# bue_steuerung.net
KiCad netlist of a schematic drawn in EAGLE
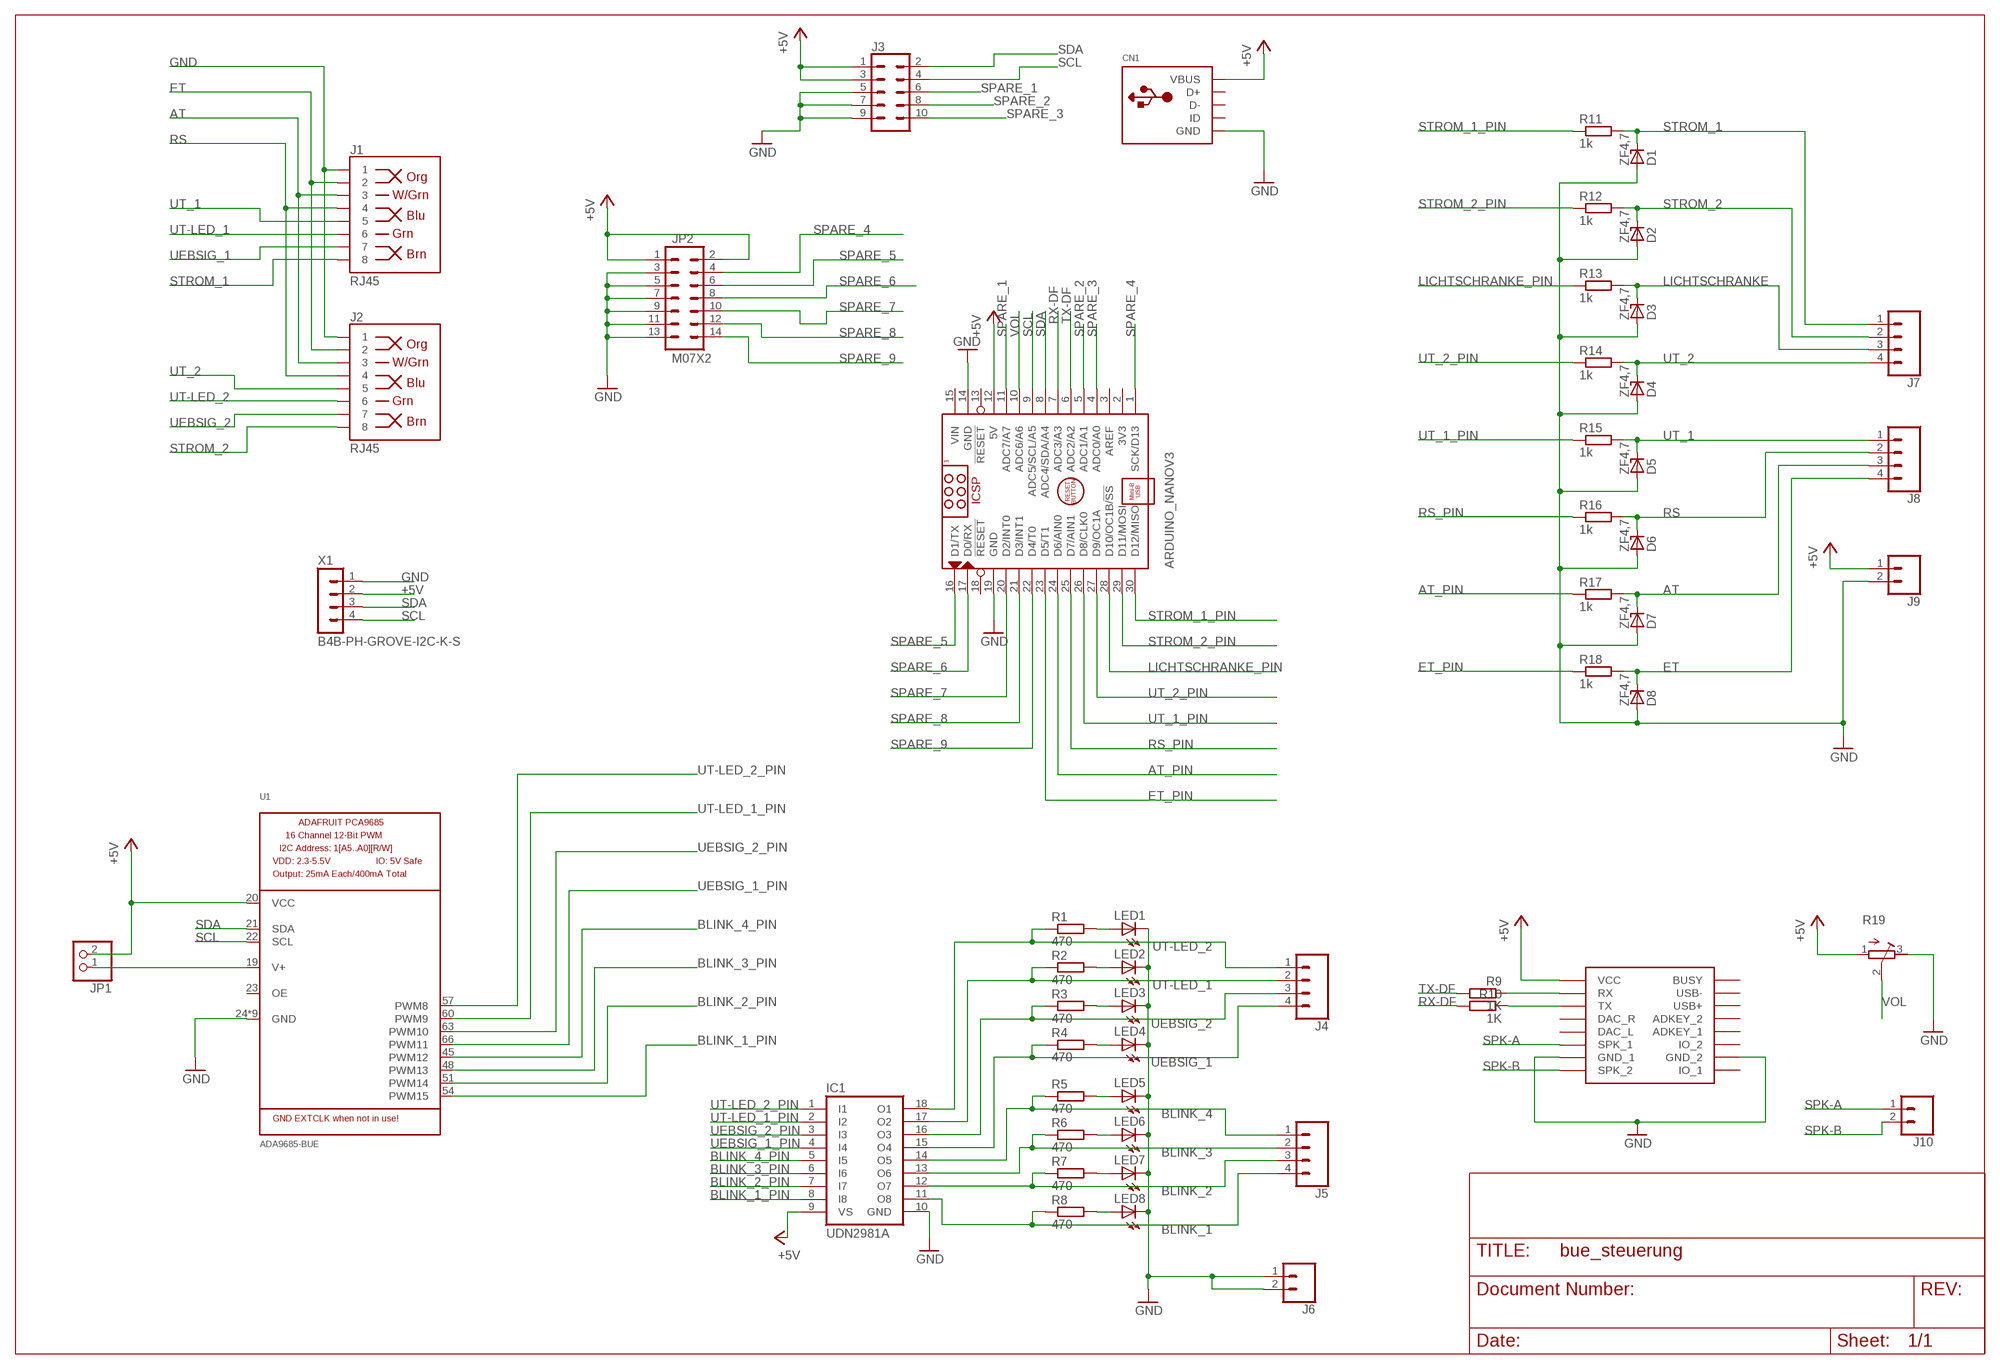
[diagram p0: schematic, sheet 1]

(export (version "E")
  (design (tool "Eeschema 10.0.6"))
  (components
    (comp (ref "ARDUINO_NANOV3")
      (value "ARDUINO_NANO")
      (footprint "eagle-import:ARDUINO_NANO")
      (libsource (lib "eagle-import") (part "ARDUINO_NANO"))
    )
    (comp (ref "CN1")
      (value "USBMOLEX")
      (footprint "eagle-import:USB-MINIB-THM-MOLEX")
      (libsource (lib "eagle-import") (part "USBMOLEX"))
    )
    (comp (ref "D1")
      (value "ZF4,7")
      (footprint "eagle-import:ZDIO-7.5")
      (libsource (lib "eagle-import") (part "ZENER-DIODEZD-7.5"))
    )
    (comp (ref "D2")
      (value "ZF4,7")
      (footprint "eagle-import:ZDIO-7.5")
      (libsource (lib "eagle-import") (part "ZENER-DIODEZD-7.5"))
    )
    (comp (ref "D3")
      (value "ZF4,7")
      (footprint "eagle-import:ZDIO-7.5")
      (libsource (lib "eagle-import") (part "ZENER-DIODEZD-7.5"))
    )
    (comp (ref "D4")
      (value "ZF4,7")
      (footprint "eagle-import:ZDIO-7.5")
      (libsource (lib "eagle-import") (part "ZENER-DIODEZD-7.5"))
    )
    (comp (ref "D5")
      (value "ZF4,7")
      (footprint "eagle-import:ZDIO-7.5")
      (libsource (lib "eagle-import") (part "ZENER-DIODEZD-7.5"))
    )
    (comp (ref "D6")
      (value "ZF4,7")
      (footprint "eagle-import:ZDIO-7.5")
      (libsource (lib "eagle-import") (part "ZENER-DIODEZD-7.5"))
    )
    (comp (ref "D7")
      (value "ZF4,7")
      (footprint "eagle-import:ZDIO-7.5")
      (libsource (lib "eagle-import") (part "ZENER-DIODEZD-7.5"))
    )
    (comp (ref "D8")
      (value "ZF4,7")
      (footprint "eagle-import:ZDIO-7.5")
      (libsource (lib "eagle-import") (part "ZENER-DIODEZD-7.5"))
    )
    (comp (ref "IC1")
      (value "UDN2981A")
      (footprint "eagle-import:DIL18")
      (libsource (lib "eagle-import") (part "UDN298A1"))
    )
    (comp (ref "J1")
      (value "RJ45")
      (footprint "eagle-import:RJ45-8")
      (libsource (lib "eagle-import") (part "RJ45-8"))
    )
    (comp (ref "J2")
      (value "RJ45")
      (footprint "eagle-import:RJ45-8")
      (libsource (lib "eagle-import") (part "RJ45-8"))
    )
    (comp (ref "J3")
      (value "CONN_05X2SHD")
      (footprint "eagle-import:2X5-SHROUDED")
      (libsource (lib "eagle-import") (part "CONN_05X2SHD"))
    )
    (comp (ref "J4")
      (value "CONN_04SCREW")
      (footprint "eagle-import:SCREWTERMINAL-3.5MM-4")
      (libsource (lib "eagle-import") (part "CONN_04SCREW"))
    )
    (comp (ref "J5")
      (value "CONN_04SCREW")
      (footprint "eagle-import:SCREWTERMINAL-3.5MM-4")
      (libsource (lib "eagle-import") (part "CONN_04SCREW"))
    )
    (comp (ref "J6")
      (value "CONN_023.5MM")
      (footprint "eagle-import:SCREWTERMINAL-3.5MM-2")
      (libsource (lib "eagle-import") (part "CONN_023.5MM"))
    )
    (comp (ref "J7")
      (value "CONN_04SCREW")
      (footprint "eagle-import:SCREWTERMINAL-3.5MM-4")
      (libsource (lib "eagle-import") (part "CONN_04SCREW"))
    )
    (comp (ref "J8")
      (value "CONN_04SCREW")
      (footprint "eagle-import:SCREWTERMINAL-3.5MM-4")
      (libsource (lib "eagle-import") (part "CONN_04SCREW"))
    )
    (comp (ref "J9")
      (value "CONN_023.5MM")
      (footprint "eagle-import:SCREWTERMINAL-3.5MM-2")
      (libsource (lib "eagle-import") (part "CONN_023.5MM"))
    )
    (comp (ref "J10")
      (value "CONN_023.5MM")
      (footprint "eagle-import:SCREWTERMINAL-3.5MM-2")
      (libsource (lib "eagle-import") (part "CONN_023.5MM"))
    )
    (comp (ref "JP1")
      (value "PINHD-1X2")
      (footprint "eagle-import:1X02")
      (libsource (lib "eagle-import") (part "PINHD-1X2"))
    )
    (comp (ref "JP2")
      (value "M07X2")
      (footprint "eagle-import:2X7-SHROUDED")
      (libsource (lib "eagle-import") (part "M07X2"))
    )
    (comp (ref "LED1")
      (value "LED3MM")
      (footprint "eagle-import:LED3MM")
      (libsource (lib "eagle-import") (part "LED3MM"))
    )
    (comp (ref "LED2")
      (value "LED3MM")
      (footprint "eagle-import:LED3MM")
      (libsource (lib "eagle-import") (part "LED3MM"))
    )
    (comp (ref "LED3")
      (value "LED3MM")
      (footprint "eagle-import:LED3MM")
      (libsource (lib "eagle-import") (part "LED3MM"))
    )
    (comp (ref "LED4")
      (value "LED3MM")
      (footprint "eagle-import:LED3MM")
      (libsource (lib "eagle-import") (part "LED3MM"))
    )
    (comp (ref "LED5")
      (value "LED3MM")
      (footprint "eagle-import:LED3MM")
      (libsource (lib "eagle-import") (part "LED3MM"))
    )
    (comp (ref "LED6")
      (value "LED3MM")
      (footprint "eagle-import:LED3MM")
      (libsource (lib "eagle-import") (part "LED3MM"))
    )
    (comp (ref "LED7")
      (value "LED3MM")
      (footprint "eagle-import:LED3MM")
      (libsource (lib "eagle-import") (part "LED3MM"))
    )
    (comp (ref "LED8")
      (value "LED3MM")
      (footprint "eagle-import:LED3MM")
      (libsource (lib "eagle-import") (part "LED3MM"))
    )
    (comp (ref "R1")
      (value "470")
      (footprint "eagle-import:0207_7")
      (libsource (lib "eagle-import") (part "resistor@1_R-EU_0207/7"))
    )
    (comp (ref "R2")
      (value "470")
      (footprint "eagle-import:0207_7")
      (libsource (lib "eagle-import") (part "resistor@1_R-EU_0207/7"))
    )
    (comp (ref "R3")
      (value "470")
      (footprint "eagle-import:0207_7")
      (libsource (lib "eagle-import") (part "resistor@1_R-EU_0207/7"))
    )
    (comp (ref "R4")
      (value "470")
      (footprint "eagle-import:0207_7")
      (libsource (lib "eagle-import") (part "resistor@1_R-EU_0207/7"))
    )
    (comp (ref "R5")
      (value "470")
      (footprint "eagle-import:0207_7")
      (libsource (lib "eagle-import") (part "resistor@1_R-EU_0207/7"))
    )
    (comp (ref "R6")
      (value "470")
      (footprint "eagle-import:0207_7")
      (libsource (lib "eagle-import") (part "resistor@1_R-EU_0207/7"))
    )
    (comp (ref "R7")
      (value "470")
      (footprint "eagle-import:0207_7")
      (libsource (lib "eagle-import") (part "resistor@1_R-EU_0207/7"))
    )
    (comp (ref "R8")
      (value "470")
      (footprint "eagle-import:0207_7")
      (libsource (lib "eagle-import") (part "resistor@1_R-EU_0207/7"))
    )
    (comp (ref "R9")
      (value "1K")
      (footprint "eagle-import:0207_7")
      (libsource (lib "eagle-import") (part "R-EU_0207/7"))
    )
    (comp (ref "R10")
      (value "1K")
      (footprint "eagle-import:0207_7")
      (libsource (lib "eagle-import") (part "R-EU_0207/7"))
    )
    (comp (ref "R11")
      (value "1k")
      (footprint "eagle-import:0207_7")
      (libsource (lib "eagle-import") (part "resistor@1_R-EU_0207/7"))
    )
    (comp (ref "R12")
      (value "1k")
      (footprint "eagle-import:0207_7")
      (libsource (lib "eagle-import") (part "resistor@1_R-EU_0207/7"))
    )
    (comp (ref "R13")
      (value "1k")
      (footprint "eagle-import:0207_7")
      (libsource (lib "eagle-import") (part "resistor@1_R-EU_0207/7"))
    )
    (comp (ref "R14")
      (value "1k")
      (footprint "eagle-import:0207_7")
      (libsource (lib "eagle-import") (part "resistor@1_R-EU_0207/7"))
    )
    (comp (ref "R15")
      (value "1k")
      (footprint "eagle-import:0207_7")
      (libsource (lib "eagle-import") (part "resistor@1_R-EU_0207/7"))
    )
    (comp (ref "R16")
      (value "1k")
      (footprint "eagle-import:0207_7")
      (libsource (lib "eagle-import") (part "resistor@1_R-EU_0207/7"))
    )
    (comp (ref "R17")
      (value "1k")
      (footprint "eagle-import:0207_7")
      (libsource (lib "eagle-import") (part "resistor@1_R-EU_0207/7"))
    )
    (comp (ref "R18")
      (value "1k")
      (footprint "eagle-import:0207_7")
      (libsource (lib "eagle-import") (part "resistor@1_R-EU_0207/7"))
    )
    (comp (ref "R19")
      (value "R-TRIMM64Y")
      (footprint "eagle-import:RTRIM64Y")
      (libsource (lib "eagle-import") (part "R-TRIMM64Y"))
    )
    (comp (ref "U1")
      (value "ADA9685-BUE")
      (footprint "eagle-import:ADA9685-BUE")
      (libsource (lib "eagle-import") (part "ADA9685-BUE"))
    )
    (comp (ref "U2")
      (value "DFPLAYER")
      (footprint "eagle-import:DFPLAYER")
      (libsource (lib "eagle-import") (part "DFPLAYER"))
    )
    (comp (ref "X1")
      (value "B4B-PH-GROVE-I2C-K-S")
      (footprint "eagle-import:B4B-PH-K-S")
      (libsource (lib "eagle-import") (part "B4B-PH-GROVE-I2C-K-S"))
    )
  )
  (nets
    (net (code "1") (name "+5V") (class "Default")
      (node (ref "ARDUINO_NANOV3") (pin "12") (pinfunction "5V_12") (pintype "power_in"))
      (node (ref "CN1") (pin "VBUS") (pinfunction "VBUS_VBUS") (pintype "power_in"))
      (node (ref "IC1") (pin "9") (pinfunction "VS_9") (pintype "passive"))
      (node (ref "J3") (pin "1") (pinfunction "1_1") (pintype "passive"))
      (node (ref "J3") (pin "3") (pinfunction "3_3") (pintype "passive"))
      (node (ref "J9") (pin "1") (pinfunction "1_1") (pintype "passive"))
      (node (ref "JP1") (pin "2") (pinfunction "2_2") (pintype "passive"))
      (node (ref "JP2") (pin "1") (pinfunction "1_1") (pintype "passive"))
      (node (ref "JP2") (pin "2") (pinfunction "2_2") (pintype "passive"))
      (node (ref "R19") (pin "1") (pinfunction "A_1") (pintype "passive"))
      (node (ref "U1") (pin "20") (pinfunction "VCC_20") (pintype "power_in"))
      (node (ref "U2") (pin "VCC") (pinfunction "VCC_VCC") (pintype "bidirectional"))
      (node (ref "X1") (pin "2") (pinfunction "3_2") (pintype "passive"))
    )
    (net (code "2") (name "/AT") (class "Default")
      (node (ref "D7") (pin "C") (pinfunction "C_C") (pintype "passive"))
      (node (ref "J1") (pin "3") (pinfunction "3_3") (pintype "bidirectional"))
      (node (ref "J2") (pin "3") (pinfunction "3_3") (pintype "bidirectional"))
      (node (ref "J8") (pin "3") (pinfunction "3_3") (pintype "passive"))
      (node (ref "R17") (pin "2") (pinfunction "2_2") (pintype "passive"))
    )
    (net (code "3") (name "/AT_PIN") (class "Default")
      (node (ref "ARDUINO_NANOV3") (pin "24") (pinfunction "D6/AIN0_24") (pintype "bidirectional"))
      (node (ref "R17") (pin "1") (pinfunction "1_1") (pintype "passive"))
    )
    (net (code "4") (name "/BLINK_1") (class "Default")
      (node (ref "IC1") (pin "11") (pinfunction "O8_11") (pintype "open_collector"))
      (node (ref "J5") (pin "4") (pinfunction "4_4") (pintype "passive"))
      (node (ref "R8") (pin "1") (pinfunction "1_1") (pintype "passive"))
    )
    (net (code "5") (name "/BLINK_1_PIN") (class "Default")
      (node (ref "IC1") (pin "8") (pinfunction "I8_8") (pintype "input"))
      (node (ref "U1") (pin "54") (pinfunction "PWM15_54") (pintype "output"))
    )
    (net (code "6") (name "/BLINK_2") (class "Default")
      (node (ref "IC1") (pin "12") (pinfunction "O7_12") (pintype "open_collector"))
      (node (ref "J5") (pin "3") (pinfunction "3_3") (pintype "passive"))
      (node (ref "R7") (pin "1") (pinfunction "1_1") (pintype "passive"))
    )
    (net (code "7") (name "/BLINK_2_PIN") (class "Default")
      (node (ref "IC1") (pin "7") (pinfunction "I7_7") (pintype "input"))
      (node (ref "U1") (pin "51") (pinfunction "PWM14_51") (pintype "output"))
    )
    (net (code "8") (name "/BLINK_3") (class "Default")
      (node (ref "IC1") (pin "13") (pinfunction "O6_13") (pintype "open_collector"))
      (node (ref "J5") (pin "2") (pinfunction "2_2") (pintype "passive"))
      (node (ref "R6") (pin "1") (pinfunction "1_1") (pintype "passive"))
    )
    (net (code "9") (name "/BLINK_3_PIN") (class "Default")
      (node (ref "IC1") (pin "6") (pinfunction "I6_6") (pintype "input"))
      (node (ref "U1") (pin "48") (pinfunction "PWM13_48") (pintype "output"))
    )
    (net (code "10") (name "/BLINK_4") (class "Default")
      (node (ref "IC1") (pin "14") (pinfunction "O5_14") (pintype "open_collector"))
      (node (ref "J5") (pin "1") (pinfunction "1_1") (pintype "passive"))
      (node (ref "R5") (pin "1") (pinfunction "1_1") (pintype "passive"))
    )
    (net (code "11") (name "/BLINK_4_PIN") (class "Default")
      (node (ref "IC1") (pin "5") (pinfunction "I5_5") (pintype "input"))
      (node (ref "U1") (pin "45") (pinfunction "PWM12_45") (pintype "output"))
    )
    (net (code "12") (name "/ET") (class "Default")
      (node (ref "D8") (pin "C") (pinfunction "C_C") (pintype "passive"))
      (node (ref "J1") (pin "2") (pinfunction "2_2") (pintype "bidirectional"))
      (node (ref "J2") (pin "2") (pinfunction "2_2") (pintype "bidirectional"))
      (node (ref "J8") (pin "4") (pinfunction "4_4") (pintype "passive"))
      (node (ref "R18") (pin "2") (pinfunction "2_2") (pintype "passive"))
    )
    (net (code "13") (name "/ET_PIN") (class "Default")
      (node (ref "ARDUINO_NANOV3") (pin "23") (pinfunction "D5/T1_23") (pintype "bidirectional"))
      (node (ref "R18") (pin "1") (pinfunction "1_1") (pintype "passive"))
    )
    (net (code "14") (name "/LICHTSCHRANKE") (class "Default")
      (node (ref "D3") (pin "C") (pinfunction "C_C") (pintype "passive"))
      (node (ref "J7") (pin "3") (pinfunction "3_3") (pintype "passive"))
      (node (ref "R13") (pin "2") (pinfunction "2_2") (pintype "passive"))
    )
    (net (code "15") (name "/LICHTSCHRANKE_PIN") (class "Default")
      (node (ref "ARDUINO_NANOV3") (pin "28") (pinfunction "D10/OC1B/~{SS}_28") (pintype "bidirectional"))
      (node (ref "R13") (pin "1") (pinfunction "1_1") (pintype "passive"))
    )
    (net (code "16") (name "/RS") (class "Default")
      (node (ref "D6") (pin "C") (pinfunction "C_C") (pintype "passive"))
      (node (ref "J1") (pin "4") (pinfunction "4_4") (pintype "bidirectional"))
      (node (ref "J2") (pin "4") (pinfunction "4_4") (pintype "bidirectional"))
      (node (ref "J8") (pin "2") (pinfunction "2_2") (pintype "passive"))
      (node (ref "R16") (pin "2") (pinfunction "2_2") (pintype "passive"))
    )
    (net (code "17") (name "/RS_PIN") (class "Default")
      (node (ref "ARDUINO_NANOV3") (pin "25") (pinfunction "D7/AIN1_25") (pintype "bidirectional"))
      (node (ref "R16") (pin "1") (pinfunction "1_1") (pintype "passive"))
    )
    (net (code "18") (name "/RX-DF") (class "Default")
      (node (ref "ARDUINO_NANOV3") (pin "7") (pinfunction "ADC3/A3_7") (pintype "bidirectional"))
      (node (ref "R10") (pin "2") (pinfunction "2_2") (pintype "passive"))
    )
    (net (code "19") (name "/SCL") (class "Default")
      (node (ref "ARDUINO_NANOV3") (pin "9") (pinfunction "ADC5/SCL/A5_9") (pintype "bidirectional"))
      (node (ref "J3") (pin "4") (pinfunction "4_4") (pintype "passive"))
      (node (ref "U1") (pin "22") (pinfunction "SCL_22") (pintype "bidirectional"))
      (node (ref "X1") (pin "4") (pinfunction "1_4") (pintype "passive"))
    )
    (net (code "20") (name "/SDA") (class "Default")
      (node (ref "ARDUINO_NANOV3") (pin "8") (pinfunction "ADC4/SDA/A4_8") (pintype "bidirectional"))
      (node (ref "J3") (pin "2") (pinfunction "2_2") (pintype "passive"))
      (node (ref "U1") (pin "21") (pinfunction "SDA_21") (pintype "bidirectional"))
      (node (ref "X1") (pin "3") (pinfunction "2_3") (pintype "passive"))
    )
    (net (code "21") (name "/SPARE_1") (class "Default")
      (node (ref "ARDUINO_NANOV3") (pin "11") (pinfunction "ADC7/A7_11") (pintype "bidirectional"))
      (node (ref "J3") (pin "6") (pinfunction "6_6") (pintype "passive"))
    )
    (net (code "22") (name "/SPARE_2") (class "Default")
      (node (ref "ARDUINO_NANOV3") (pin "5") (pinfunction "ADC1/A1_5") (pintype "bidirectional"))
      (node (ref "J3") (pin "8") (pinfunction "8_8") (pintype "passive"))
    )
    (net (code "23") (name "/SPARE_3") (class "Default")
      (node (ref "ARDUINO_NANOV3") (pin "4") (pinfunction "ADC0/A0_4") (pintype "bidirectional"))
      (node (ref "J3") (pin "10") (pinfunction "10_10") (pintype "passive"))
    )
    (net (code "24") (name "/SPARE_4") (class "Default")
      (node (ref "ARDUINO_NANOV3") (pin "1") (pinfunction "SCK/D13_1") (pintype "bidirectional"))
      (node (ref "JP2") (pin "4") (pinfunction "4_4") (pintype "passive"))
    )
    (net (code "25") (name "/SPARE_5") (class "Default")
      (node (ref "ARDUINO_NANOV3") (pin "16") (pinfunction "D1/TX_16") (pintype "bidirectional"))
      (node (ref "JP2") (pin "6") (pinfunction "6_6") (pintype "passive"))
    )
    (net (code "26") (name "/SPARE_6") (class "Default")
      (node (ref "ARDUINO_NANOV3") (pin "17") (pinfunction "D0/RX_17") (pintype "bidirectional"))
      (node (ref "JP2") (pin "8") (pinfunction "8_8") (pintype "passive"))
    )
    (net (code "27") (name "/SPARE_7") (class "Default")
      (node (ref "ARDUINO_NANOV3") (pin "20") (pinfunction "D2/INT0_20") (pintype "bidirectional"))
      (node (ref "JP2") (pin "10") (pinfunction "10_10") (pintype "passive"))
    )
    (net (code "28") (name "/SPARE_8") (class "Default")
      (node (ref "ARDUINO_NANOV3") (pin "21") (pinfunction "D3/INT1_21") (pintype "bidirectional"))
      (node (ref "JP2") (pin "12") (pinfunction "12_12") (pintype "passive"))
    )
    (net (code "29") (name "/SPARE_9") (class "Default")
      (node (ref "ARDUINO_NANOV3") (pin "22") (pinfunction "D4/T0_22") (pintype "bidirectional"))
      (node (ref "JP2") (pin "14") (pinfunction "14_14") (pintype "passive"))
    )
    (net (code "30") (name "/SPK-A") (class "Default")
      (node (ref "J10") (pin "1") (pinfunction "1_1") (pintype "passive"))
      (node (ref "U2") (pin "SPK1") (pinfunction "SPK_1_SPK1") (pintype "bidirectional"))
    )
    (net (code "31") (name "/SPK-B") (class "Default")
      (node (ref "J10") (pin "2") (pinfunction "2_2") (pintype "passive"))
      (node (ref "U2") (pin "SPK2") (pinfunction "SPK_2_SPK2") (pintype "bidirectional"))
    )
    (net (code "32") (name "/STROM_1") (class "Default")
      (node (ref "D1") (pin "C") (pinfunction "C_C") (pintype "passive"))
      (node (ref "J1") (pin "8") (pinfunction "8_8") (pintype "bidirectional"))
      (node (ref "J7") (pin "1") (pinfunction "1_1") (pintype "passive"))
      (node (ref "R11") (pin "2") (pinfunction "2_2") (pintype "passive"))
    )
    (net (code "33") (name "/STROM_1_PIN") (class "Default")
      (node (ref "ARDUINO_NANOV3") (pin "30") (pinfunction "D12/MISO_30") (pintype "bidirectional"))
      (node (ref "R11") (pin "1") (pinfunction "1_1") (pintype "passive"))
    )
    (net (code "34") (name "/STROM_2") (class "Default")
      (node (ref "D2") (pin "C") (pinfunction "C_C") (pintype "passive"))
      (node (ref "J2") (pin "8") (pinfunction "8_8") (pintype "bidirectional"))
      (node (ref "J7") (pin "2") (pinfunction "2_2") (pintype "passive"))
      (node (ref "R12") (pin "2") (pinfunction "2_2") (pintype "passive"))
    )
    (net (code "35") (name "/STROM_2_PIN") (class "Default")
      (node (ref "ARDUINO_NANOV3") (pin "29") (pinfunction "D11/MOSI_29") (pintype "bidirectional"))
      (node (ref "R12") (pin "1") (pinfunction "1_1") (pintype "passive"))
    )
    (net (code "36") (name "/TX-DF") (class "Default")
      (node (ref "ARDUINO_NANOV3") (pin "6") (pinfunction "ADC2/A2_6") (pintype "bidirectional"))
      (node (ref "R9") (pin "2") (pinfunction "2_2") (pintype "passive"))
    )
    (net (code "37") (name "/UEBSIG_1") (class "Default")
      (node (ref "IC1") (pin "15") (pinfunction "O4_15") (pintype "open_collector"))
      (node (ref "J1") (pin "7") (pinfunction "7_7") (pintype "bidirectional"))
      (node (ref "J4") (pin "4") (pinfunction "4_4") (pintype "passive"))
      (node (ref "R4") (pin "1") (pinfunction "1_1") (pintype "passive"))
    )
    (net (code "38") (name "/UEBSIG_1_PIN") (class "Default")
      (node (ref "IC1") (pin "4") (pinfunction "I4_4") (pintype "input"))
      (node (ref "U1") (pin "66") (pinfunction "PWM11_66") (pintype "output"))
    )
    (net (code "39") (name "/UEBSIG_2") (class "Default")
      (node (ref "IC1") (pin "16") (pinfunction "O3_16") (pintype "open_collector"))
      (node (ref "J2") (pin "7") (pinfunction "7_7") (pintype "bidirectional"))
      (node (ref "J4") (pin "3") (pinfunction "3_3") (pintype "passive"))
      (node (ref "R3") (pin "1") (pinfunction "1_1") (pintype "passive"))
    )
    (net (code "40") (name "/UEBSIG_2_PIN") (class "Default")
      (node (ref "IC1") (pin "3") (pinfunction "I3_3") (pintype "input"))
      (node (ref "U1") (pin "63") (pinfunction "PWM10_63") (pintype "output"))
    )
    (net (code "41") (name "/UT-LED_1") (class "Default")
      (node (ref "IC1") (pin "17") (pinfunction "O2_17") (pintype "open_collector"))
      (node (ref "J1") (pin "6") (pinfunction "6_6") (pintype "bidirectional"))
      (node (ref "J4") (pin "2") (pinfunction "2_2") (pintype "passive"))
      (node (ref "R2") (pin "1") (pinfunction "1_1") (pintype "passive"))
    )
    (net (code "42") (name "/UT-LED_1_PIN") (class "Default")
      (node (ref "IC1") (pin "2") (pinfunction "I2_2") (pintype "input"))
      (node (ref "U1") (pin "60") (pinfunction "PWM9_60") (pintype "output"))
    )
    (net (code "43") (name "/UT-LED_2") (class "Default")
      (node (ref "IC1") (pin "18") (pinfunction "O1_18") (pintype "open_collector"))
      (node (ref "J2") (pin "6") (pinfunction "6_6") (pintype "bidirectional"))
      (node (ref "J4") (pin "1") (pinfunction "1_1") (pintype "passive"))
      (node (ref "R1") (pin "1") (pinfunction "1_1") (pintype "passive"))
    )
    (net (code "44") (name "/UT-LED_2_PIN") (class "Default")
      (node (ref "IC1") (pin "1") (pinfunction "I1_1") (pintype "input"))
      (node (ref "U1") (pin "57") (pinfunction "PWM8_57") (pintype "output"))
    )
    (net (code "45") (name "/UT_1") (class "Default")
      (node (ref "D5") (pin "C") (pinfunction "C_C") (pintype "passive"))
      (node (ref "J1") (pin "5") (pinfunction "5_5") (pintype "bidirectional"))
      (node (ref "J8") (pin "1") (pinfunction "1_1") (pintype "passive"))
      (node (ref "R15") (pin "2") (pinfunction "2_2") (pintype "passive"))
    )
    (net (code "46") (name "/UT_1_PIN") (class "Default")
      (node (ref "ARDUINO_NANOV3") (pin "26") (pinfunction "D8/CLK0_26") (pintype "bidirectional"))
      (node (ref "R15") (pin "1") (pinfunction "1_1") (pintype "passive"))
    )
    (net (code "47") (name "/UT_2") (class "Default")
      (node (ref "D4") (pin "C") (pinfunction "C_C") (pintype "passive"))
      (node (ref "J2") (pin "5") (pinfunction "5_5") (pintype "bidirectional"))
      (node (ref "J7") (pin "4") (pinfunction "4_4") (pintype "passive"))
      (node (ref "R14") (pin "2") (pinfunction "2_2") (pintype "passive"))
    )
    (net (code "48") (name "/UT_2_PIN") (class "Default")
      (node (ref "ARDUINO_NANOV3") (pin "27") (pinfunction "D9/OC1A_27") (pintype "bidirectional"))
      (node (ref "R14") (pin "1") (pinfunction "1_1") (pintype "passive"))
    )
    (net (code "49") (name "/VIN") (class "Default")
      (node (ref "ARDUINO_NANOV3") (pin "15") (pinfunction "VIN_15") (pintype "power_in"))
    )
    (net (code "50") (name "/VOL") (class "Default")
      (node (ref "ARDUINO_NANOV3") (pin "10") (pinfunction "ADC6/A6_10") (pintype "bidirectional"))
      (node (ref "R19") (pin "2") (pinfunction "S_2") (pintype "passive"))
    )
    (net (code "51") (name "GND") (class "Default")
      (node (ref "ARDUINO_NANOV3") (pin "14") (pinfunction "GND_14") (pintype "power_in"))
      (node (ref "ARDUINO_NANOV3") (pin "19") (pinfunction "GND_19") (pintype "power_in"))
      (node (ref "CN1") (pin "GND") (pinfunction "GND_GND") (pintype "power_in"))
      (node (ref "D1") (pin "A") (pinfunction "A_A") (pintype "passive"))
      (node (ref "D2") (pin "A") (pinfunction "A_A") (pintype "passive"))
      (node (ref "D3") (pin "A") (pinfunction "A_A") (pintype "passive"))
      (node (ref "D4") (pin "A") (pinfunction "A_A") (pintype "passive"))
      (node (ref "D5") (pin "A") (pinfunction "A_A") (pintype "passive"))
      (node (ref "D6") (pin "A") (pinfunction "A_A") (pintype "passive"))
      (node (ref "D7") (pin "A") (pinfunction "A_A") (pintype "passive"))
      (node (ref "D8") (pin "A") (pinfunction "A_A") (pintype "passive"))
      (node (ref "IC1") (pin "10") (pinfunction "GND_10") (pintype "power_in"))
      (node (ref "J1") (pin "1") (pinfunction "1_1") (pintype "bidirectional"))
      (node (ref "J2") (pin "1") (pinfunction "1_1") (pintype "bidirectional"))
      (node (ref "J3") (pin "5") (pinfunction "5_5") (pintype "passive"))
      (node (ref "J3") (pin "7") (pinfunction "7_7") (pintype "passive"))
      (node (ref "J3") (pin "9") (pinfunction "9_9") (pintype "passive"))
      (node (ref "J6") (pin "1") (pinfunction "1_1") (pintype "passive"))
      (node (ref "J6") (pin "2") (pinfunction "2_2") (pintype "passive"))
      (node (ref "J9") (pin "2") (pinfunction "2_2") (pintype "passive"))
      (node (ref "JP2") (pin "11") (pinfunction "11_11") (pintype "passive"))
      (node (ref "JP2") (pin "13") (pinfunction "13_13") (pintype "passive"))
      (node (ref "JP2") (pin "3") (pinfunction "3_3") (pintype "passive"))
      (node (ref "JP2") (pin "5") (pinfunction "5_5") (pintype "passive"))
      (node (ref "JP2") (pin "7") (pinfunction "7_7") (pintype "passive"))
      (node (ref "JP2") (pin "9") (pinfunction "9_9") (pintype "passive"))
      (node (ref "LED1") (pin "K") (pinfunction "C_K") (pintype "passive"))
      (node (ref "LED2") (pin "K") (pinfunction "C_K") (pintype "passive"))
      (node (ref "LED3") (pin "K") (pinfunction "C_K") (pintype "passive"))
      (node (ref "LED4") (pin "K") (pinfunction "C_K") (pintype "passive"))
      (node (ref "LED5") (pin "K") (pinfunction "C_K") (pintype "passive"))
      (node (ref "LED6") (pin "K") (pinfunction "C_K") (pintype "passive"))
      (node (ref "LED7") (pin "K") (pinfunction "C_K") (pintype "passive"))
      (node (ref "LED8") (pin "K") (pinfunction "C_K") (pintype "passive"))
      (node (ref "R19") (pin "3") (pinfunction "E_3") (pintype "passive"))
      (node (ref "U1") (pin "24") (pinfunction "GND_24") (pintype "power_in"))
      (node (ref "U1") (pin "43") (pinfunction "GND_43") (pintype "power_in"))
      (node (ref "U1") (pin "46") (pinfunction "GND_46") (pintype "power_in"))
      (node (ref "U1") (pin "49") (pinfunction "GND_49") (pintype "power_in"))
      (node (ref "U1") (pin "52") (pinfunction "GND_52") (pintype "power_in"))
      (node (ref "U1") (pin "55") (pinfunction "GND_55") (pintype "power_in"))
      (node (ref "U1") (pin "58") (pinfunction "GND_58") (pintype "power_in"))
      (node (ref "U1") (pin "61") (pinfunction "GND_61") (pintype "power_in"))
      (node (ref "U1") (pin "64") (pinfunction "GND_64") (pintype "power_in"))
      (node (ref "U2") (pin "GND_1") (pinfunction "GND_1_GND_1") (pintype "bidirectional"))
      (node (ref "U2") (pin "GND_2") (pinfunction "GND_2_GND_2") (pintype "bidirectional"))
      (node (ref "X1") (pin "1") (pinfunction "4_1") (pintype "passive"))
    )
    (net (code "52") (name "Net-(LED1-PadA)") (class "Default")
      (node (ref "LED1") (pin "A") (pinfunction "A_A") (pintype "passive"))
      (node (ref "R1") (pin "2") (pinfunction "2_2") (pintype "passive"))
    )
    (net (code "53") (name "Net-(LED2-PadA)") (class "Default")
      (node (ref "LED2") (pin "A") (pinfunction "A_A") (pintype "passive"))
      (node (ref "R2") (pin "2") (pinfunction "2_2") (pintype "passive"))
    )
    (net (code "54") (name "Net-(LED3-PadA)") (class "Default")
      (node (ref "LED3") (pin "A") (pinfunction "A_A") (pintype "passive"))
      (node (ref "R3") (pin "2") (pinfunction "2_2") (pintype "passive"))
    )
    (net (code "55") (name "Net-(LED4-PadA)") (class "Default")
      (node (ref "LED4") (pin "A") (pinfunction "A_A") (pintype "passive"))
      (node (ref "R4") (pin "2") (pinfunction "2_2") (pintype "passive"))
    )
    (net (code "56") (name "Net-(LED5-PadA)") (class "Default")
      (node (ref "LED5") (pin "A") (pinfunction "A_A") (pintype "passive"))
      (node (ref "R5") (pin "2") (pinfunction "2_2") (pintype "passive"))
    )
    (net (code "57") (name "Net-(LED6-PadA)") (class "Default")
      (node (ref "LED6") (pin "A") (pinfunction "A_A") (pintype "passive"))
      (node (ref "R6") (pin "2") (pinfunction "2_2") (pintype "passive"))
    )
    (net (code "58") (name "Net-(LED7-PadA)") (class "Default")
      (node (ref "LED7") (pin "A") (pinfunction "A_A") (pintype "passive"))
      (node (ref "R7") (pin "2") (pinfunction "2_2") (pintype "passive"))
    )
    (net (code "59") (name "Net-(LED8-PadA)") (class "Default")
      (node (ref "LED8") (pin "A") (pinfunction "A_A") (pintype "passive"))
      (node (ref "R8") (pin "2") (pinfunction "2_2") (pintype "passive"))
    )
    (net (code "60") (name "Net-(R9-Pad1)") (class "Default")
      (node (ref "R9") (pin "1") (pinfunction "1_1") (pintype "passive"))
      (node (ref "U2") (pin "RX") (pinfunction "RX_RX") (pintype "bidirectional"))
    )
    (net (code "61") (name "Net-(R10-Pad1)") (class "Default")
      (node (ref "R10") (pin "1") (pinfunction "1_1") (pintype "passive"))
      (node (ref "U2") (pin "TX") (pinfunction "TX_TX") (pintype "bidirectional"))
    )
    (net (code "62") (name "Net-(U1-V+)") (class "Default")
      (node (ref "JP1") (pin "1") (pinfunction "1_1") (pintype "passive"))
      (node (ref "U1") (pin "19") (pinfunction "V+_19") (pintype "input"))
    )
    (net (code "63") (name "unconnected-(ARDUINO_NANOV3-3V3-Pad2)") (class "Default")
      (node (ref "ARDUINO_NANOV3") (pin "2") (pinfunction "3V3_2") (pintype "output"))
    )
    (net (code "64") (name "unconnected-(ARDUINO_NANOV3-AREF-Pad3)") (class "Default")
      (node (ref "ARDUINO_NANOV3") (pin "3") (pinfunction "AREF_3") (pintype "input"))
    )
    (net (code "65") (name "unconnected-(ARDUINO_NANOV3-~{RESET}-Pad13)") (class "Default")
      (node (ref "ARDUINO_NANOV3") (pin "13") (pinfunction "~{RESET}_13") (pintype "input"))
    )
    (net (code "66") (name "unconnected-(ARDUINO_NANOV3-~{RESET}-Pad18)") (class "Default")
      (node (ref "ARDUINO_NANOV3") (pin "18") (pinfunction "~{RESET}_18") (pintype "input"))
    )
    (net (code "67") (name "unconnected-(CN1-PadD+)") (class "Default")
      (node (ref "CN1") (pin "D+") (pinfunction "D+_D+") (pintype "bidirectional"))
    )
    (net (code "68") (name "unconnected-(CN1-PadD-)") (class "Default")
      (node (ref "CN1") (pin "D-") (pinfunction "D-_D-") (pintype "bidirectional"))
    )
    (net (code "69") (name "unconnected-(CN1-PadID)") (class "Default")
      (node (ref "CN1") (pin "ID") (pinfunction "ID_ID") (pintype "bidirectional"))
    )
    (net (code "70") (name "unconnected-(U1-OE-Pad23)") (class "Default")
      (node (ref "U1") (pin "23") (pinfunction "OE_23") (pintype "input"))
    )
    (net (code "71") (name "unconnected-(U2-ADKEY_1-PadADKEY1)") (class "Default")
      (node (ref "U2") (pin "ADKEY1") (pinfunction "ADKEY_1_ADKEY1") (pintype "bidirectional"))
    )
    (net (code "72") (name "unconnected-(U2-ADKEY_2-PadADKEY2)") (class "Default")
      (node (ref "U2") (pin "ADKEY2") (pinfunction "ADKEY_2_ADKEY2") (pintype "bidirectional"))
    )
    (net (code "73") (name "unconnected-(U2-IO_1-PadIO1)") (class "Default")
      (node (ref "U2") (pin "IO1") (pinfunction "IO_1_IO1") (pintype "bidirectional"))
    )
    (net (code "74") (name "unconnected-(U2-IO_2-PadIO2)") (class "Default")
      (node (ref "U2") (pin "IO2") (pinfunction "IO_2_IO2") (pintype "bidirectional"))
    )
    (net (code "75") (name "unconnected-(U2-PadBUSY)") (class "Default")
      (node (ref "U2") (pin "BUSY") (pinfunction "BUSY_BUSY") (pintype "bidirectional"))
    )
    (net (code "76") (name "unconnected-(U2-PadDAC_L)") (class "Default")
      (node (ref "U2") (pin "DAC_L") (pinfunction "DAC_L_DAC_L") (pintype "bidirectional"))
    )
    (net (code "77") (name "unconnected-(U2-PadDAC_R)") (class "Default")
      (node (ref "U2") (pin "DAC_R") (pinfunction "DAC_R_DAC_R") (pintype "bidirectional"))
    )
    (net (code "78") (name "unconnected-(U2-PadUSB+)") (class "Default")
      (node (ref "U2") (pin "USB+") (pinfunction "USB+_USB+") (pintype "bidirectional"))
    )
    (net (code "79") (name "unconnected-(U2-PadUSB-)") (class "Default")
      (node (ref "U2") (pin "USB-") (pinfunction "USB-_USB-") (pintype "bidirectional"))
    )
  )
)
